# Power.net
KiCad netlist of a schematic drawn in Altium Designer
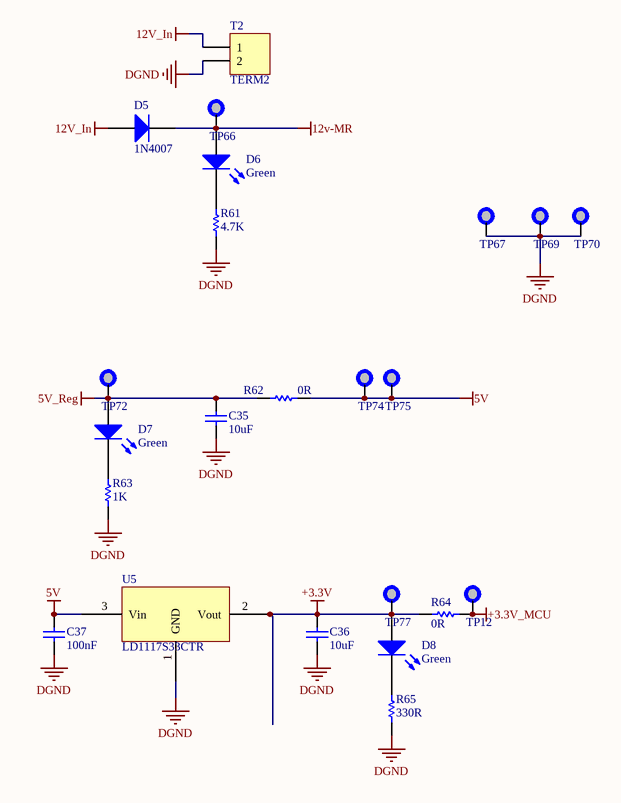
[diagram p0: Power.SchDoc]

(export (version "E")
  (design (tool "Eeschema 10.0.6"))
  (components
    (comp (ref "C35")
      (value "10uF")
      (footprint "1206C")
      (description "LOW ESR")
      (fields (field (name "Comment") "10uF/50V") (field (name "PUBLISHER") "Altium Limited"))
      (libsource (lib "Miscellaneous Devices") (part "Cap"))
    )
    (comp (ref "C36")
      (value "10uF")
      (footprint "1206C")
      (description "LOW ESR")
      (fields (field (name "Comment") "10uF/50V") (field (name "PUBLISHER") "Altium Limited"))
      (libsource (lib "Miscellaneous Devices") (part "Cap"))
    )
    (comp (ref "C37")
      (value "100nF")
      (footprint "0603c")
      (description "LOW ESR")
      (fields (field (name "PUBLISHER") "Altium Limited"))
      (libsource (lib "Miscellaneous Devices") (part "Cap"))
    )
    (comp (ref "D5")
      (value "1N4007")
      (footprint "SMC")
      (description "1n4007")
      (fields (field (name "PUBLISHER") "Altium Limited"))
      (libsource (lib "Miscellaneous Devices") (part "Diode"))
    )
    (comp (ref "D6")
      (value "Green")
      (footprint "0805LED")
      (fields (field (name "PUBLISHER") "Altium Limited"))
      (libsource (lib "Miscellaneous Devices") (part "LED0"))
    )
    (comp (ref "D7")
      (value "Green")
      (footprint "0805LED")
      (fields (field (name "PUBLISHER") "Altium Limited"))
      (libsource (lib "Miscellaneous Devices") (part "LED0"))
    )
    (comp (ref "D8")
      (value "Green")
      (footprint "0805LED")
      (fields (field (name "PUBLISHER") "Altium Limited"))
      (libsource (lib "Miscellaneous Devices") (part "LED0"))
    )
    (comp (ref "R61")
      (value "4.7K")
      (footprint "0805")
      (description "Resistor")
      (fields (field (name "PUBLISHER") "Altium Limited"))
      (libsource (lib "Miscellaneous Devices") (part "Res1"))
    )
    (comp (ref "R62")
      (value "0R")
      (footprint "1206")
      (description "Resistor")
      (fields (field (name "PUBLISHER") "Altium Limited"))
      (libsource (lib "Miscellaneous Devices") (part "Res1"))
    )
    (comp (ref "R63")
      (value "1K")
      (footprint "0805")
      (description "Resistor")
      (fields (field (name "PUBLISHER") "Altium Limited"))
      (libsource (lib "Miscellaneous Devices") (part "Res1"))
    )
    (comp (ref "R64")
      (value "0R")
      (footprint "1206")
      (description "Resistor")
      (fields (field (name "PUBLISHER") "Altium Limited"))
      (libsource (lib "Miscellaneous Devices") (part "Res1"))
    )
    (comp (ref "R65")
      (value "330R")
      (footprint "0805")
      (description "Resistor")
      (fields (field (name "PUBLISHER") "Altium Limited"))
      (libsource (lib "Miscellaneous Devices") (part "Res1"))
    )
    (comp (ref "T2")
      (value "TERM2")
      (footprint "term2")
      (description "Header, 2-Pin")
      (fields (field (name "PUBLISHER") "Altium Limited"))
      (libsource (lib "Miscellaneous Connectors") (part "Header 2"))
    )
    (comp (ref "TP12") (value "TestPoint") (footprint "TP") (libsource (lib "SchlibV0.1") (part "TestPoint")))
    (comp (ref "TP66") (value "TestPoint") (footprint "TP") (libsource (lib "SchlibV0.1") (part "TestPoint")))
    (comp (ref "TP67") (value "TestPoint") (footprint "TP") (libsource (lib "SchlibV0.1") (part "TestPoint")))
    (comp (ref "TP69") (value "TestPoint") (footprint "TP") (libsource (lib "SchlibV0.1") (part "TestPoint")))
    (comp (ref "TP70") (value "TestPoint") (footprint "TP") (libsource (lib "SchlibV0.1") (part "TestPoint")))
    (comp (ref "TP72") (value "TestPoint") (footprint "TP") (libsource (lib "SchlibV0.1") (part "TestPoint")))
    (comp (ref "TP74") (value "TestPoint") (footprint "TP") (libsource (lib "SchlibV0.1") (part "TestPoint")))
    (comp (ref "TP75") (value "TestPoint") (footprint "TP") (libsource (lib "SchlibV0.1") (part "TestPoint")))
    (comp (ref "TP77") (value "TestPoint") (footprint "TP") (libsource (lib "SchlibV0.1") (part "TestPoint")))
    (comp (ref "U5")
      (value "LD1117S33CTR")
      (footprint "sot223")
      (libsource (lib "SchlibV0.1") (part "AMS1117"))
    )
  )
  (nets
    (net (code "1") (name "+3.3V") (class "Default")
      (node (ref "C36") (pin "2") (pinfunction "2_2") (pintype "passive"))
      (node (ref "D8") (pin "1") (pinfunction "A_1") (pintype "passive"))
      (node (ref "R64") (pin "1") (pinfunction "1_1") (pintype "passive"))
      (node (ref "TP77") (pin "1") (pintype "passive"))
      (node (ref "U5") (pin "2") (pinfunction "Vout_2") (pintype "passive"))
      (node (ref "U5") (pin "4") (pinfunction "Vout_4") (pintype "passive"))
    )
    (net (code "2") (name "+3.3V_MCU") (class "Default")
      (node (ref "R64") (pin "2") (pinfunction "2_2") (pintype "passive"))
      (node (ref "TP12") (pin "1") (pintype "passive"))
    )
    (net (code "3") (name "5V") (class "Default")
      (node (ref "C37") (pin "1") (pinfunction "1_1") (pintype "passive"))
      (node (ref "R62") (pin "2") (pinfunction "2_2") (pintype "passive"))
      (node (ref "TP74") (pin "1") (pintype "passive"))
      (node (ref "TP75") (pin "1") (pintype "passive"))
      (node (ref "U5") (pin "3") (pinfunction "Vin_3") (pintype "passive"))
    )
    (net (code "4") (name "5V_Reg") (class "Default")
      (node (ref "C35") (pin "2") (pinfunction "2_2") (pintype "passive"))
      (node (ref "D7") (pin "1") (pinfunction "A_1") (pintype "passive"))
      (node (ref "R62") (pin "1") (pinfunction "1_1") (pintype "passive"))
      (node (ref "TP72") (pin "1") (pintype "passive"))
    )
    (net (code "5") (name "12V_In") (class "Default")
      (node (ref "D5") (pin "1") (pinfunction "A_1") (pintype "passive"))
      (node (ref "T2") (pin "1") (pinfunction "1_1") (pintype "passive"))
    )
    (net (code "6") (name "12v-MR") (class "Default")
      (node (ref "D5") (pin "2") (pinfunction "K_2") (pintype "passive"))
      (node (ref "D6") (pin "1") (pinfunction "A_1") (pintype "passive"))
      (node (ref "TP66") (pin "1") (pintype "passive"))
    )
    (net (code "7") (name "DGND") (class "Default")
      (node (ref "C35") (pin "1") (pinfunction "1_1") (pintype "passive"))
      (node (ref "C36") (pin "1") (pinfunction "1_1") (pintype "passive"))
      (node (ref "C37") (pin "2") (pinfunction "2_2") (pintype "passive"))
      (node (ref "R61") (pin "1") (pinfunction "1_1") (pintype "passive"))
      (node (ref "R63") (pin "1") (pinfunction "1_1") (pintype "passive"))
      (node (ref "R65") (pin "1") (pinfunction "1_1") (pintype "passive"))
      (node (ref "T2") (pin "2") (pinfunction "2_2") (pintype "passive"))
      (node (ref "TP67") (pin "1") (pintype "passive"))
      (node (ref "TP69") (pin "1") (pintype "passive"))
      (node (ref "TP70") (pin "1") (pintype "passive"))
      (node (ref "U5") (pin "1") (pinfunction "GND_1") (pintype "passive"))
    )
    (net (code "8") (name "Net-(D6-K)") (class "Default")
      (node (ref "D6") (pin "2") (pinfunction "K_2") (pintype "passive"))
      (node (ref "R61") (pin "2") (pinfunction "2_2") (pintype "passive"))
    )
    (net (code "9") (name "Net-(D7-K)") (class "Default")
      (node (ref "D7") (pin "2") (pinfunction "K_2") (pintype "passive"))
      (node (ref "R63") (pin "2") (pinfunction "2_2") (pintype "passive"))
    )
    (net (code "10") (name "Net-(D8-K)") (class "Default")
      (node (ref "D8") (pin "2") (pinfunction "K_2") (pintype "passive"))
      (node (ref "R65") (pin "2") (pinfunction "2_2") (pintype "passive"))
    )
  )
)
